# 105358-3SC001-01-B_BlockDiagram.net
KiCad netlist of a schematic drawn in Altium Designer
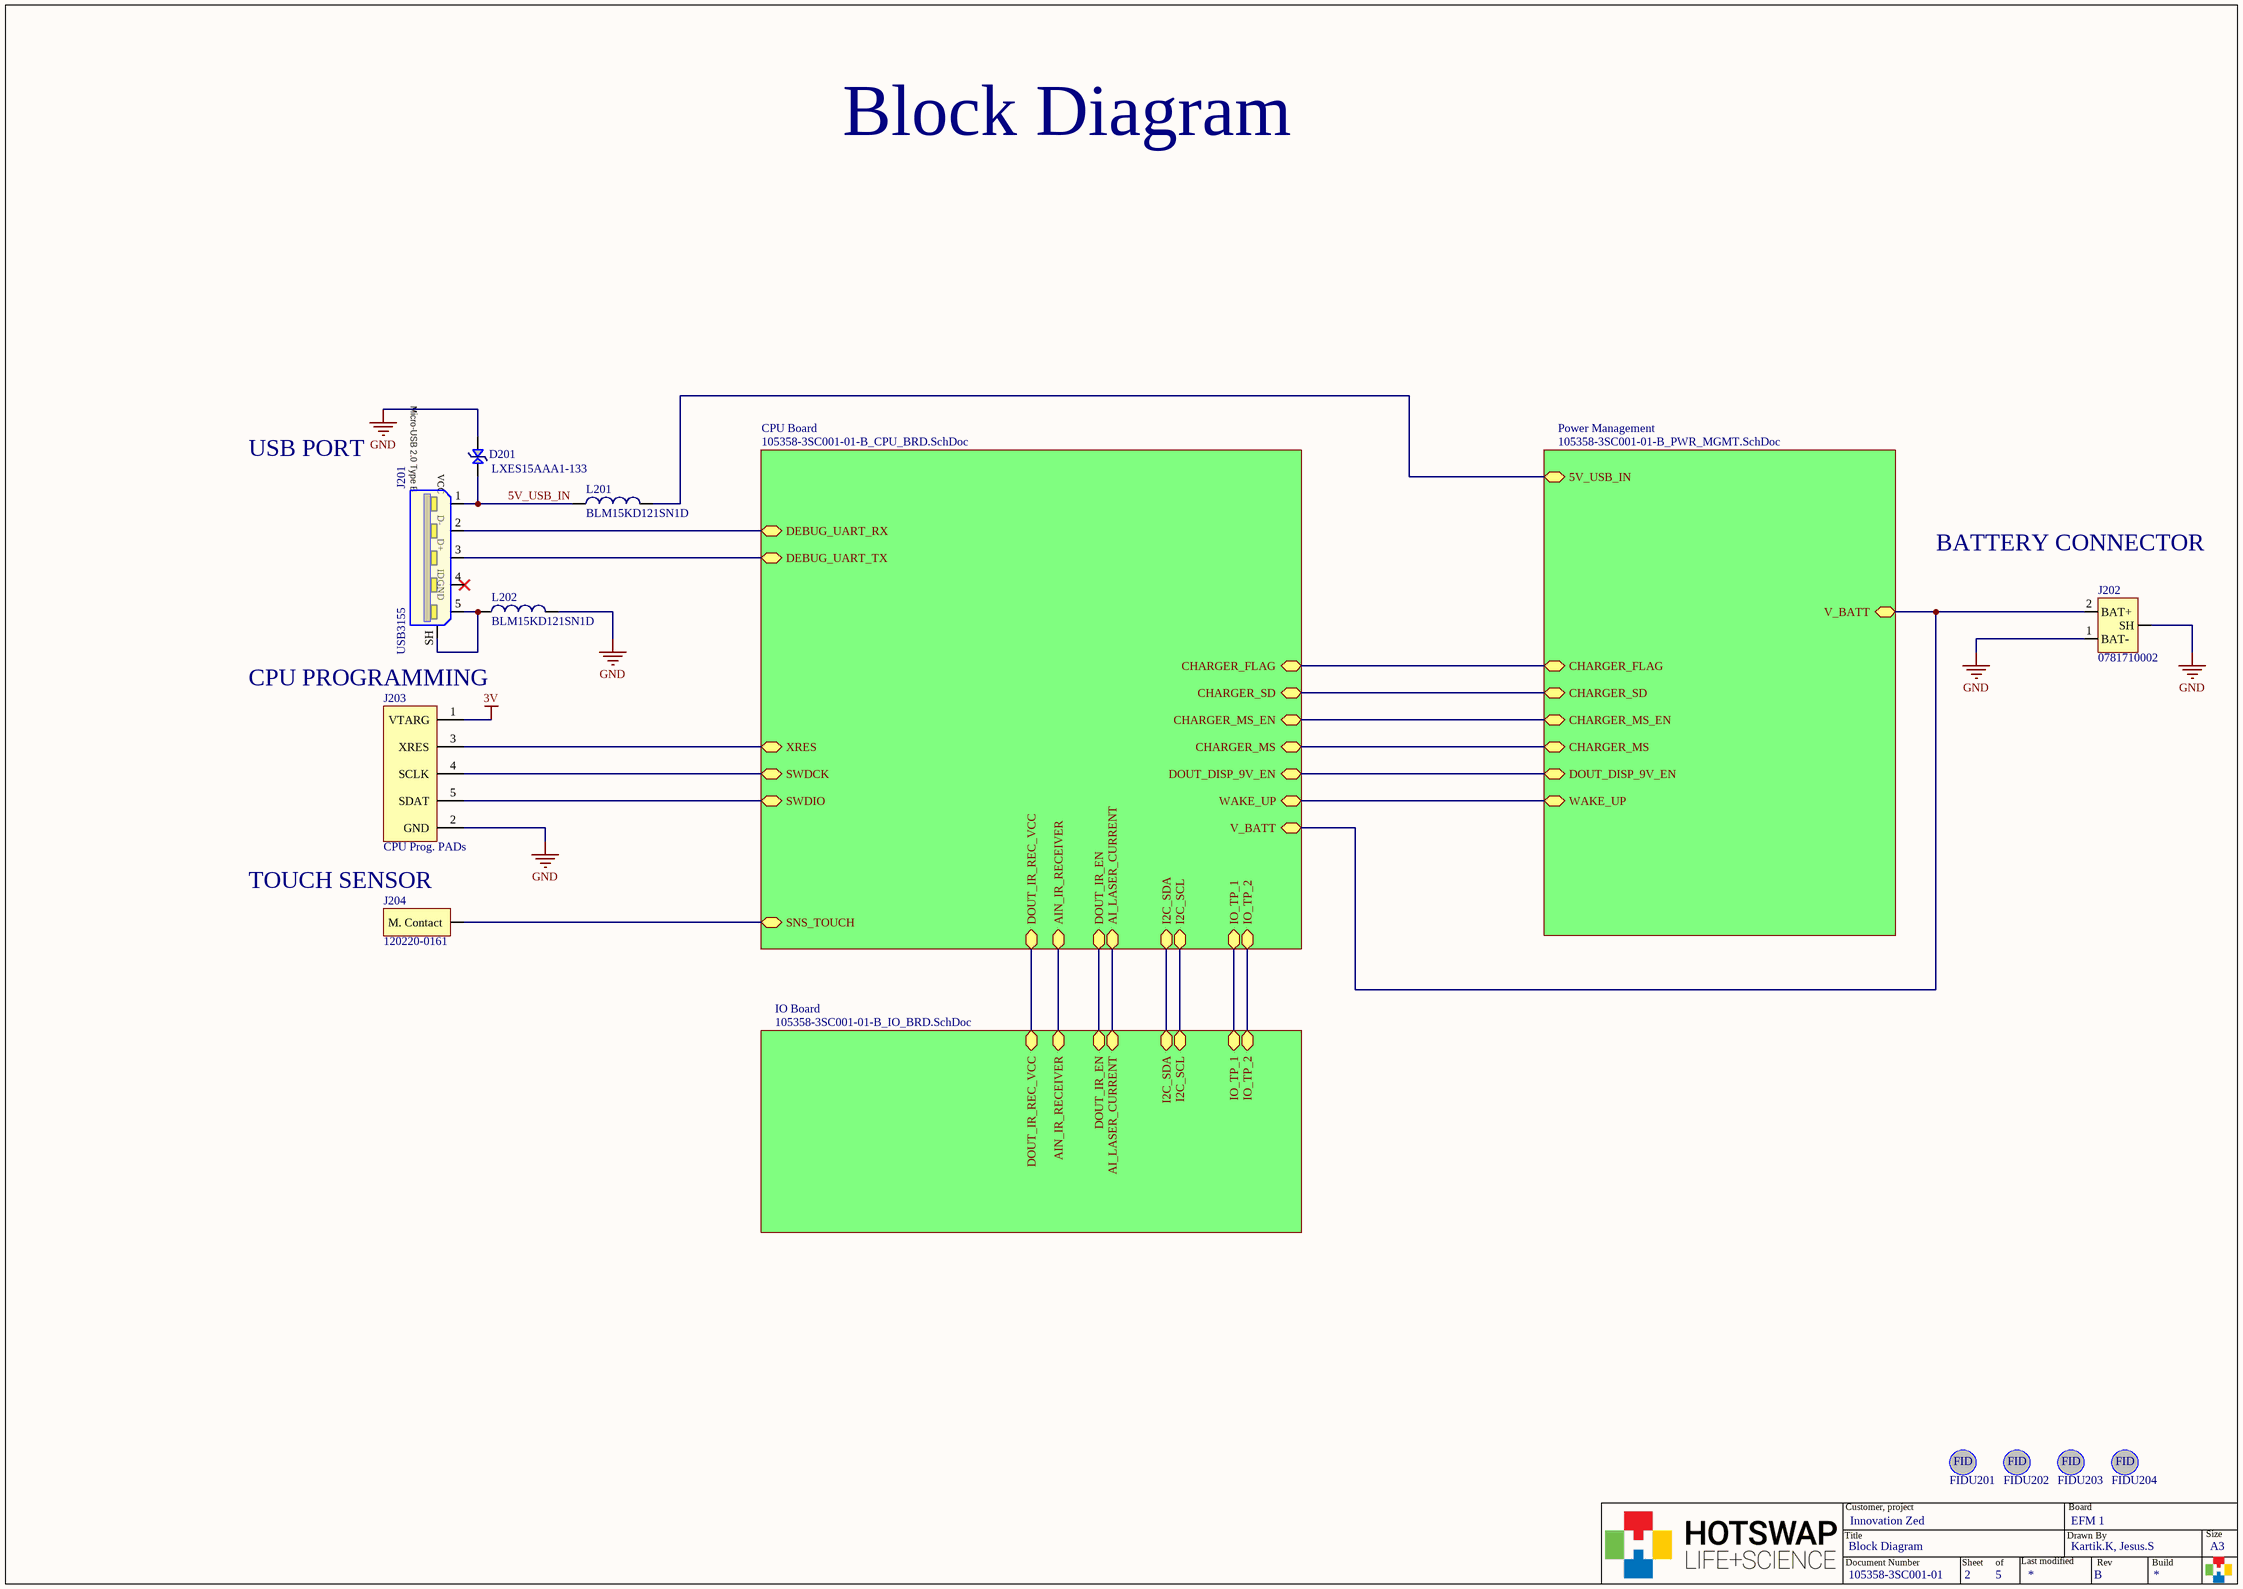
[diagram p0: 105358-3SC001-01-B_BlockDiagram.SchDoc]

(export (version "E")
  (design (tool "Eeschema 10.0.6"))
  (components
    (comp (ref "D201")
      (value "LXES15AAA1-133")
      (footprint "0402C-GENERIC")
      (description "TVS DIODE 15VWM 0402")
      (fields
        (field (name "MANUFACTURER") "Murata Electronics North America")
        (field (name "DIGI-KEY PART NUMBER") "490-13209-1-ND")
      )
      (libsource (lib "ConnectMedical") (part "TVS DIODE 15VWM 0402"))
    )
    (comp (ref "FIDU201")
      (value "FIDU-miniROUND")
      (footprint "FIDU-MINI-ROUND")
      (libsource (lib "ConnectMedical") (part "FIDU-miniROUND"))
    )
    (comp (ref "FIDU202")
      (value "FIDU-miniROUND")
      (footprint "FIDU-MINI-ROUND")
      (libsource (lib "ConnectMedical") (part "FIDU-miniROUND"))
    )
    (comp (ref "FIDU203")
      (value "FIDU-miniROUND")
      (footprint "FIDU-MINI-ROUND")
      (libsource (lib "ConnectMedical") (part "FIDU-miniROUND"))
    )
    (comp (ref "FIDU204")
      (value "FIDU-miniROUND")
      (footprint "FIDU-MINI-ROUND")
      (libsource (lib "ConnectMedical") (part "FIDU-miniROUND"))
    )
    (comp (ref "J201")
      (value "USB3155")
      (footprint "USB3155")
      (description "CONN RCPT USB-mini B 2.0 5POS SLD")
      (fields
        (field (name "MANUFACTURER") "GCT (GLOBAL CONNECTOR TECHNOLOGY)")
        (field (name "MANUFACTURER PART NUMBER") "USB3155-30-A")
      )
      (libsource (lib "ConnectMedical") (part "USB3155"))
    )
    (comp (ref "J202")
      (value "0781710002")
      (footprint "PAD 0781710002")
      (description "1.20MM WTB HEADER VERT 2POS")
      (fields (field (name "MANUFACTURER") "Molex, LLC") (field (name "DIGI-KEY PART NUMBER") "WM4459CT-ND"))
      (libsource (lib "ConnectMedical") (part "CONNECTOR 1.20MM WTB HEADER VERT 2POS"))
    )
    (comp (ref "J203")
      (value "CPU Prog. PADs")
      (footprint "PAD PROGRAMMING")
      (description "CPU Programming PADs")
      (libsource (lib "ConnectMedical") (part "PROGRAMMING PADS"))
    )
    (comp (ref "J204")
      (value "120220-0161")
      (footprint "PAD 1.0x3.76mm")
      (description "UNIVERSAL CONTACT 2.5MM SMD")
      (fields
        (field (name "MANUFACTURER") "ITT Cannon, LLC")
        (field (name "DIGI-KEY PART NUMBER") "1003-1009-1-ND")
      )
      (libsource (lib "ConnectMedical") (part "UNIVERSAL_CONTACT_2.5MM SMD"))
    )
    (comp (ref "L201")
      (value "BLM15KD121SN1D")
      (footprint "0402L_High Speed")
      (description "FERRITE BEAD 120 OHM 0402 1LN")
      (fields
        (field (name "DIGI-KEY PART NUMBER") "490-15015-1-ND")
        (field (name "MANUFACTURER") "Murata Electronics North America")
      )
      (libsource (lib "ConnectMedical") (part "0402L_FERRITE BEAD"))
    )
    (comp (ref "L202")
      (value "BLM15KD121SN1D")
      (footprint "0402L_High Speed")
      (description "FERRITE BEAD 120 OHM 0402 1LN")
      (fields
        (field (name "DIGI-KEY PART NUMBER") "490-15015-1-ND")
        (field (name "MANUFACTURER") "Murata Electronics North America")
      )
      (libsource (lib "ConnectMedical") (part "0402L_FERRITE BEAD"))
    )
  )
  (nets
    (net (code "1") (name "/5V_USB_IN") (class "Default")
      (node (ref "D201") (pin "2") (pinfunction "2_2") (pintype "passive"))
      (node (ref "J201") (pin "1") (pinfunction "VCC_1") (pintype "passive"))
      (node (ref "L201") (pin "1") (pinfunction "1_1") (pintype "passive"))
    )
    (net (code "2") (name "/5V_USB_IN_1") (class "Default")
      (node (ref "L201") (pin "2") (pinfunction "2_2") (pintype "passive"))
    )
    (net (code "9") (name "/DEBUG_UART_RX") (class "Default")
      (node (ref "J201") (pin "2") (pinfunction "D-_2") (pintype "passive"))
    )
    (net (code "10") (name "/DEBUG_UART_TX") (class "Default")
      (node (ref "J201") (pin "3") (pinfunction "D+_3") (pintype "passive"))
    )
    (net (code "18") (name "/SNS_TOUCH") (class "Default")
      (node (ref "J204") (pin "1") (pinfunction "M._Contact_1") (pintype "passive"))
    )
    (net (code "19") (name "/SWDCK") (class "Default")
      (node (ref "J203") (pin "4") (pinfunction "SCLK_4") (pintype "passive"))
    )
    (net (code "20") (name "/SWDIO") (class "Default")
      (node (ref "J203") (pin "5") (pinfunction "SDAT_5") (pintype "passive"))
    )
    (net (code "21") (name "/V_BATT") (class "Default")
      (node (ref "J202") (pin "2") (pinfunction "BAT+_2") (pintype "passive"))
    )
    (net (code "23") (name "/XRES") (class "Default")
      (node (ref "J203") (pin "3") (pinfunction "XRES_3") (pintype "passive"))
    )
    (net (code "24") (name "3V") (class "Default")
      (node (ref "J203") (pin "1") (pinfunction "VTARG_1") (pintype "passive"))
    )
    (net (code "25") (name "GND") (class "Default")
      (node (ref "D201") (pin "1") (pinfunction "1_1") (pintype "passive"))
      (node (ref "J202") (pin "1") (pinfunction "BAT-_1") (pintype "passive"))
      (node (ref "J202") (pin "3") (pinfunction "SH_3") (pintype "passive"))
      (node (ref "J203") (pin "2") (pinfunction "GND_2") (pintype "passive"))
      (node (ref "L202") (pin "2") (pinfunction "2_2") (pintype "passive"))
    )
    (net (code "26") (name "Net-(J201-GND)") (class "Default")
      (node (ref "J201") (pin "5") (pinfunction "GND_5") (pintype "passive"))
      (node (ref "J201") (pin "SH") (pinfunction "Shell_SH") (pintype "passive"))
      (node (ref "L202") (pin "1") (pinfunction "1_1") (pintype "passive"))
    )
    (net (code "27") (name "unconnected-(J201-ID-Pad4)") (class "Default")
      (node (ref "J201") (pin "4") (pinfunction "ID_4") (pintype "passive+no_connect"))
    )
  )
)
